# SCH_Atari_ST_sidecart_prototype_shared_b.net
KiCad netlist of a schematic drawn in EasyEDA
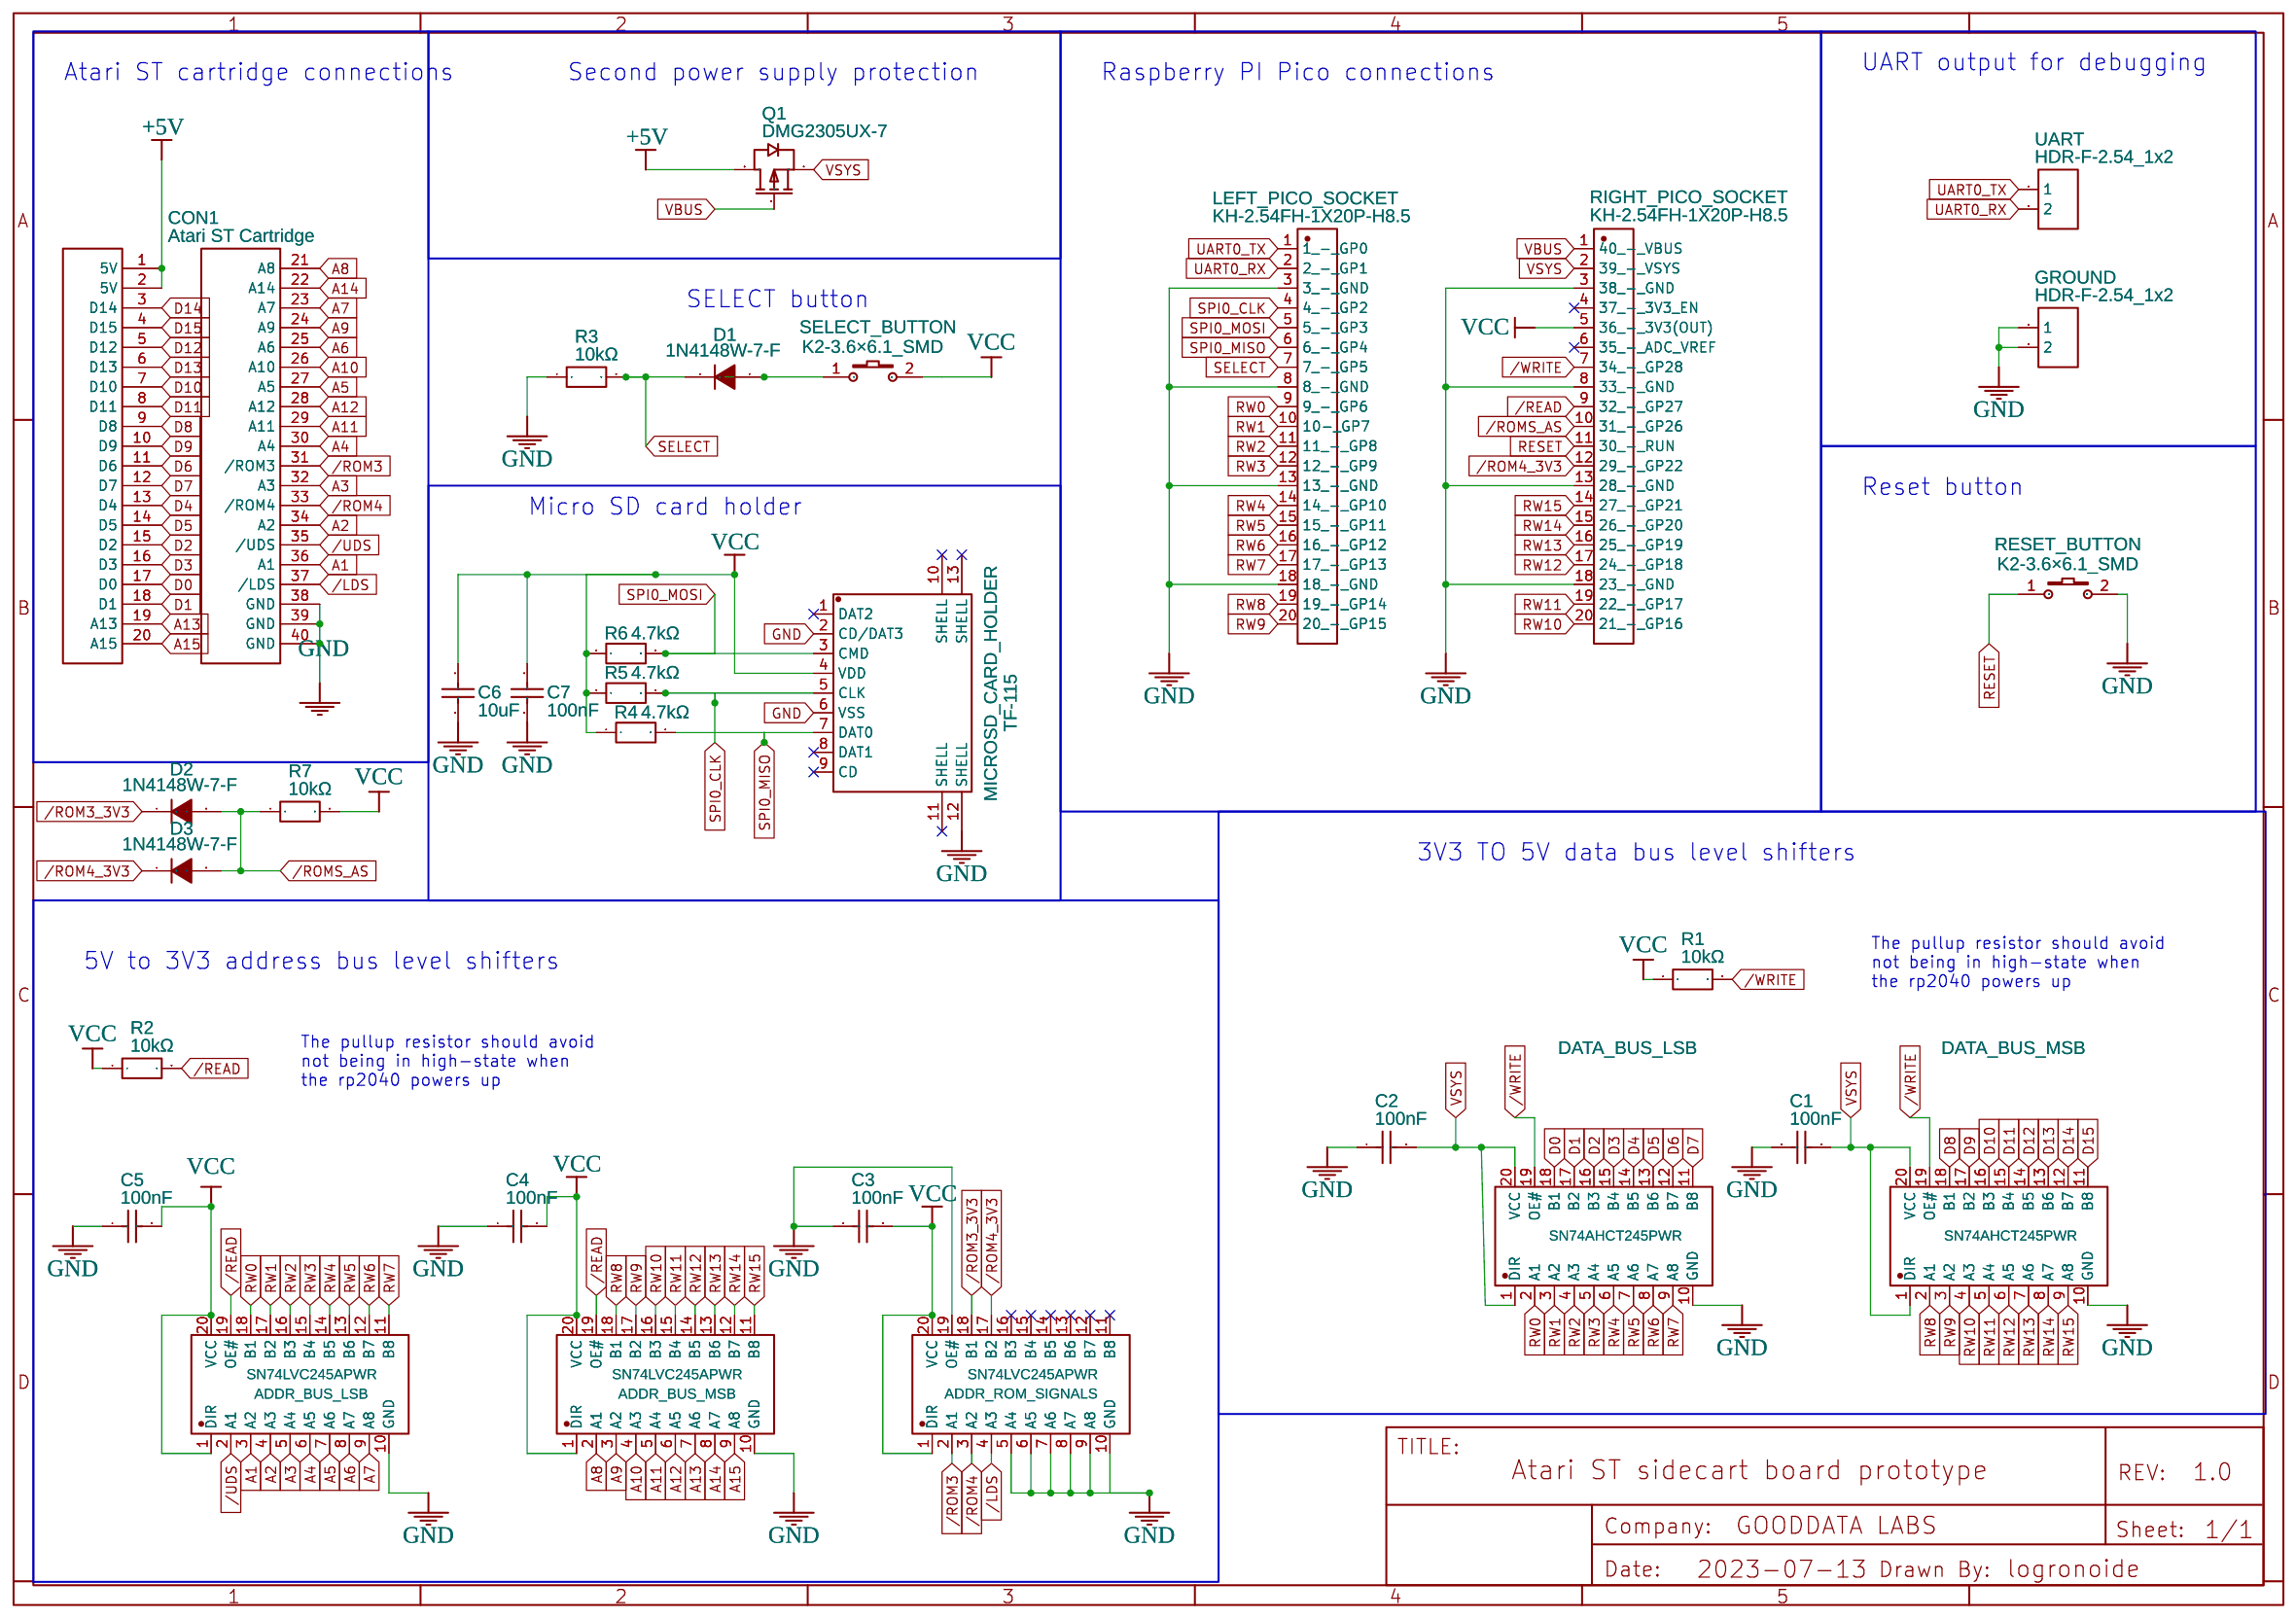
[diagram p0: schematic sheet]

(export (version "E")
  (design (tool "Eeschema 10.0.6"))
  (components
    (comp (ref "ADDR_BUS_LSB")
      (value "SN74LVC245APWR")
      (fields (field (name "Manufacturer") "TI(德州仪器)"))
      (libsource (lib "") (part "SN74LVC245ANG4_1"))
    )
    (comp (ref "ADDR_BUS_MSB")
      (value "SN74LVC245APWR")
      (fields (field (name "Manufacturer") "TI(德州仪器)"))
      (libsource (lib "") (part "SN74LVC245ANG4_2"))
    )
    (comp (ref "ADDR_ROM_SIGNALS")
      (value "SN74LVC245APWR")
      (fields (field (name "Manufacturer") "TI(德州仪器)"))
      (libsource (lib "") (part "SN74LVC245ANG4"))
    )
    (comp (ref "C1")
      (value "100nF")
      (fields
        (field (name "Manufacturer Part") "C0603C104K5RACAUTO")
        (field (name "Manufacturer") "KEMET(基美)")
      )
      (libsource (lib "") (part "C0603C104K5RACAUTO"))
    )
    (comp (ref "C2")
      (value "100nF")
      (fields
        (field (name "Manufacturer Part") "C0603C104K5RACAUTO")
        (field (name "Manufacturer") "KEMET(基美)")
      )
      (libsource (lib "") (part "C0603C104K5RACAUTO"))
    )
    (comp (ref "C3")
      (value "100nF")
      (fields
        (field (name "Manufacturer Part") "C0603C104K5RACAUTO")
        (field (name "Manufacturer") "KEMET(基美)")
      )
      (libsource (lib "") (part "C0603C104K5RACAUTO"))
    )
    (comp (ref "C4")
      (value "100nF")
      (fields
        (field (name "Manufacturer Part") "C0603C104K5RACAUTO")
        (field (name "Manufacturer") "KEMET(基美)")
      )
      (libsource (lib "") (part "C0603C104K5RACAUTO"))
    )
    (comp (ref "C5")
      (value "100nF")
      (fields
        (field (name "Manufacturer Part") "C0603C104K5RACAUTO")
        (field (name "Manufacturer") "KEMET(基美)")
      )
      (libsource (lib "") (part "C0603C104K5RACAUTO"))
    )
    (comp (ref "C6")
      (value "10uF")
      (fields
        (field (name "Manufacturer Part") "CC0603MRX5R7BB106")
        (field (name "Manufacturer") "YAGEO(国巨)")
      )
      (libsource (lib "") (part "CC0603MRX5R7BB106"))
    )
    (comp (ref "C7")
      (value "100nF")
      (fields
        (field (name "Manufacturer Part") "C0603C104K5RACAUTO")
        (field (name "Manufacturer") "KEMET(基美)")
      )
      (libsource (lib "") (part "C0603C104K5RACAUTO_1"))
    )
    (comp (ref "CON1") (value "Atari ST Cartridge") (libsource (lib "") (part "Unknown_90_-590")))
    (comp (ref "D1")
      (value "1N4148W-7-F")
      (fields (field (name "Manufacturer") "DIODES(美台)"))
      (libsource (lib "") (part "1N4148W-7-F"))
    )
    (comp (ref "D2")
      (value "1N4148W-7-F")
      (fields (field (name "Manufacturer") "DIODES(美台)"))
      (libsource (lib "") (part "1N4148W-7-F"))
    )
    (comp (ref "D3")
      (value "1N4148W-7-F")
      (fields (field (name "Manufacturer") "DIODES(美台)"))
      (libsource (lib "") (part "1N4148W-7-F"))
    )
    (comp (ref "DATA_BUS_LSB")
      (value "SN74AHCT245PWR")
      (fields (field (name "Manufacturer") "TI(德州仪器)"))
      (libsource (lib "") (part "SN74AHCT245N_1"))
    )
    (comp (ref "DATA_BUS_MSB")
      (value "SN74AHCT245PWR")
      (fields (field (name "Manufacturer") "TI(德州仪器)"))
      (libsource (lib "") (part "SN74AHCT245N"))
    )
    (comp (ref "GROUND") (value "HDR-F-2.54_1x2") (libsource (lib "") (part "HDR-F-2.54_1x2")))
    (comp (ref "LEFT_PICO_SOCKET")
      (value "KH-2.54FH-1X20P-H8.5")
      (fields (field (name "Manufacturer") "kinghelm(金航标)"))
      (libsource (lib "") (part "KH-2.54FH-1X20P-H8.5_1"))
    )
    (comp (ref "MICROSD_CARD_HOLDER")
      (value "TF-115")
      (fields (field (name "Manufacturer") "XUNPU(讯普)"))
      (libsource (lib "") (part "TF-115"))
    )
    (comp (ref "Q1")
      (value "DMG2305UX-7")
      (fields (field (name "Manufacturer") "DIODES(美台)"))
      (libsource (lib "") (part "DMG2305UX-7"))
    )
    (comp (ref "R1")
      (value "10kΩ")
      (fields (field (name "Manufacturer Part") "RT0603DRE0710KL") (field (name "Manufacturer") "YAGEO(国巨)"))
      (libsource (lib "") (part "RT0603DRE0710KL"))
    )
    (comp (ref "R2")
      (value "10kΩ")
      (fields (field (name "Manufacturer Part") "RT0603DRE0710KL") (field (name "Manufacturer") "YAGEO(国巨)"))
      (libsource (lib "") (part "RT0603DRE0710KL"))
    )
    (comp (ref "R3")
      (value "10kΩ")
      (fields (field (name "Manufacturer Part") "RT0603DRE0710KL") (field (name "Manufacturer") "YAGEO(国巨)"))
      (libsource (lib "") (part "RT0603DRE0710KL"))
    )
    (comp (ref "R4")
      (value "4.7kΩ")
      (fields
        (field (name "Manufacturer Part") "CR0603F4K70P05Z")
        (field (name "Manufacturer") "EVER OHMS(天二科技)")
      )
      (libsource (lib "") (part "CR0603F4K70P05Z"))
    )
    (comp (ref "R5")
      (value "4.7kΩ")
      (fields
        (field (name "Manufacturer Part") "CR0603F4K70P05Z")
        (field (name "Manufacturer") "EVER OHMS(天二科技)")
      )
      (libsource (lib "") (part "CR0603F4K70P05Z"))
    )
    (comp (ref "R6")
      (value "4.7kΩ")
      (fields
        (field (name "Manufacturer Part") "CR0603F4K70P05Z")
        (field (name "Manufacturer") "EVER OHMS(天二科技)")
      )
      (libsource (lib "") (part "CR0603F4K70P05Z"))
    )
    (comp (ref "R7")
      (value "10kΩ")
      (fields (field (name "Manufacturer Part") "RT0603DRE0710KL") (field (name "Manufacturer") "YAGEO(国巨)"))
      (libsource (lib "") (part "RT0603DRE0710KL"))
    )
    (comp (ref "RESET_BUTTON")
      (value "K2-3.6×6.1_SMD")
      (fields (field (name "Manufacturer Part") "K2-1107ST-A4SW-06"))
      (libsource (lib "") (part "K2-3.6×6.1_SMD_1"))
    )
    (comp (ref "RIGHT_PICO_SOCKET")
      (value "KH-2.54FH-1X20P-H8.5")
      (fields (field (name "Manufacturer") "kinghelm(金航标)"))
      (libsource (lib "") (part "KH-2.54FH-1X20P-H8.5"))
    )
    (comp (ref "SELECT_BUTTON")
      (value "K2-3.6×6.1_SMD")
      (fields (field (name "Manufacturer Part") "K2-1107ST-A4SW-06"))
      (libsource (lib "") (part "K2-3.6×6.1_SMD"))
    )
    (comp (ref "UART") (value "HDR-F-2.54_1x2") (libsource (lib "") (part "HDR-F-2.54_1x2_1")))
  )
  (nets
    (net (code "1") (name "+5V") (class "Default")
      (node (ref "CON1") (pin "1") (pinfunction "5V_1") (pintype "unspecified"))
      (node (ref "CON1") (pin "2") (pinfunction "5V_2") (pintype "unspecified"))
      (node (ref "Q1") (pin "3") (pinfunction "D_3") (pintype "unspecified"))
    )
    (net (code "2") (name "A1") (class "Default")
      (node (ref "ADDR_BUS_LSB") (pin "3") (pinfunction "A2_3") (pintype "unspecified"))
      (node (ref "CON1") (pin "36") (pinfunction "A1_36") (pintype "unspecified"))
    )
    (net (code "3") (name "A2") (class "Default")
      (node (ref "ADDR_BUS_LSB") (pin "4") (pinfunction "A3_4") (pintype "unspecified"))
      (node (ref "CON1") (pin "34") (pinfunction "A2_34") (pintype "unspecified"))
    )
    (net (code "4") (name "A3") (class "Default")
      (node (ref "ADDR_BUS_LSB") (pin "5") (pinfunction "A4_5") (pintype "unspecified"))
      (node (ref "CON1") (pin "32") (pinfunction "A3_32") (pintype "unspecified"))
    )
    (net (code "5") (name "A4") (class "Default")
      (node (ref "ADDR_BUS_LSB") (pin "6") (pinfunction "A5_6") (pintype "unspecified"))
      (node (ref "CON1") (pin "30") (pinfunction "A4_30") (pintype "unspecified"))
    )
    (net (code "6") (name "A5") (class "Default")
      (node (ref "ADDR_BUS_LSB") (pin "7") (pinfunction "A6_7") (pintype "unspecified"))
      (node (ref "CON1") (pin "27") (pinfunction "A5_27") (pintype "unspecified"))
    )
    (net (code "7") (name "A6") (class "Default")
      (node (ref "ADDR_BUS_LSB") (pin "8") (pinfunction "A7_8") (pintype "unspecified"))
      (node (ref "CON1") (pin "25") (pinfunction "A6_25") (pintype "unspecified"))
    )
    (net (code "8") (name "A7") (class "Default")
      (node (ref "ADDR_BUS_LSB") (pin "9") (pinfunction "A8_9") (pintype "unspecified"))
      (node (ref "CON1") (pin "23") (pinfunction "A7_23") (pintype "unspecified"))
    )
    (net (code "9") (name "A8") (class "Default")
      (node (ref "ADDR_BUS_MSB") (pin "2") (pinfunction "A1_2") (pintype "unspecified"))
      (node (ref "CON1") (pin "21") (pinfunction "A8_21") (pintype "unspecified"))
    )
    (net (code "10") (name "A9") (class "Default")
      (node (ref "ADDR_BUS_MSB") (pin "3") (pinfunction "A2_3") (pintype "unspecified"))
      (node (ref "CON1") (pin "24") (pinfunction "A9_24") (pintype "unspecified"))
    )
    (net (code "11") (name "A10") (class "Default")
      (node (ref "ADDR_BUS_MSB") (pin "4") (pinfunction "A3_4") (pintype "unspecified"))
      (node (ref "CON1") (pin "26") (pinfunction "A10_26") (pintype "unspecified"))
    )
    (net (code "12") (name "A11") (class "Default")
      (node (ref "ADDR_BUS_MSB") (pin "5") (pinfunction "A4_5") (pintype "unspecified"))
      (node (ref "CON1") (pin "29") (pinfunction "A11_29") (pintype "unspecified"))
    )
    (net (code "13") (name "A12") (class "Default")
      (node (ref "ADDR_BUS_MSB") (pin "6") (pinfunction "A5_6") (pintype "unspecified"))
      (node (ref "CON1") (pin "28") (pinfunction "A12_28") (pintype "unspecified"))
    )
    (net (code "14") (name "A13") (class "Default")
      (node (ref "ADDR_BUS_MSB") (pin "7") (pinfunction "A6_7") (pintype "unspecified"))
      (node (ref "CON1") (pin "19") (pinfunction "A13_19") (pintype "unspecified"))
    )
    (net (code "15") (name "A14") (class "Default")
      (node (ref "ADDR_BUS_MSB") (pin "8") (pinfunction "A7_8") (pintype "unspecified"))
      (node (ref "CON1") (pin "22") (pinfunction "A14_22") (pintype "unspecified"))
    )
    (net (code "16") (name "A15") (class "Default")
      (node (ref "ADDR_BUS_MSB") (pin "9") (pinfunction "A8_9") (pintype "unspecified"))
      (node (ref "CON1") (pin "20") (pinfunction "A15_20") (pintype "unspecified"))
    )
    (net (code "17") (name "D0") (class "Default")
      (node (ref "CON1") (pin "17") (pinfunction "D0_17") (pintype "unspecified"))
      (node (ref "DATA_BUS_LSB") (pin "18") (pinfunction "B1_18") (pintype "unspecified"))
    )
    (net (code "18") (name "D1") (class "Default")
      (node (ref "CON1") (pin "18") (pinfunction "D1_18") (pintype "unspecified"))
      (node (ref "DATA_BUS_LSB") (pin "17") (pinfunction "B2_17") (pintype "unspecified"))
    )
    (net (code "19") (name "D2") (class "Default")
      (node (ref "CON1") (pin "15") (pinfunction "D2_15") (pintype "unspecified"))
      (node (ref "DATA_BUS_LSB") (pin "16") (pinfunction "B3_16") (pintype "unspecified"))
    )
    (net (code "20") (name "D3") (class "Default")
      (node (ref "CON1") (pin "16") (pinfunction "D3_16") (pintype "unspecified"))
      (node (ref "DATA_BUS_LSB") (pin "15") (pinfunction "B4_15") (pintype "unspecified"))
    )
    (net (code "21") (name "D4") (class "Default")
      (node (ref "CON1") (pin "13") (pinfunction "D4_13") (pintype "unspecified"))
      (node (ref "DATA_BUS_LSB") (pin "14") (pinfunction "B5_14") (pintype "unspecified"))
    )
    (net (code "22") (name "D5") (class "Default")
      (node (ref "CON1") (pin "14") (pinfunction "D5_14") (pintype "unspecified"))
      (node (ref "DATA_BUS_LSB") (pin "13") (pinfunction "B6_13") (pintype "unspecified"))
    )
    (net (code "23") (name "D6") (class "Default")
      (node (ref "CON1") (pin "11") (pinfunction "D6_11") (pintype "unspecified"))
      (node (ref "DATA_BUS_LSB") (pin "12") (pinfunction "B7_12") (pintype "unspecified"))
    )
    (net (code "24") (name "D7") (class "Default")
      (node (ref "CON1") (pin "12") (pinfunction "D7_12") (pintype "unspecified"))
      (node (ref "DATA_BUS_LSB") (pin "11") (pinfunction "B8_11") (pintype "unspecified"))
    )
    (net (code "25") (name "D8") (class "Default")
      (node (ref "CON1") (pin "9") (pinfunction "D8_9") (pintype "unspecified"))
      (node (ref "DATA_BUS_MSB") (pin "18") (pinfunction "B1_18") (pintype "unspecified"))
    )
    (net (code "26") (name "D9") (class "Default")
      (node (ref "CON1") (pin "10") (pinfunction "D9_10") (pintype "unspecified"))
      (node (ref "DATA_BUS_MSB") (pin "17") (pinfunction "B2_17") (pintype "unspecified"))
    )
    (net (code "27") (name "D10") (class "Default")
      (node (ref "CON1") (pin "7") (pinfunction "D10_7") (pintype "unspecified"))
      (node (ref "DATA_BUS_MSB") (pin "16") (pinfunction "B3_16") (pintype "unspecified"))
    )
    (net (code "28") (name "D11") (class "Default")
      (node (ref "CON1") (pin "8") (pinfunction "D11_8") (pintype "unspecified"))
      (node (ref "DATA_BUS_MSB") (pin "15") (pinfunction "B4_15") (pintype "unspecified"))
    )
    (net (code "29") (name "D12") (class "Default")
      (node (ref "CON1") (pin "5") (pinfunction "D12_5") (pintype "unspecified"))
      (node (ref "DATA_BUS_MSB") (pin "14") (pinfunction "B5_14") (pintype "unspecified"))
    )
    (net (code "30") (name "D13") (class "Default")
      (node (ref "CON1") (pin "6") (pinfunction "D13_6") (pintype "unspecified"))
      (node (ref "DATA_BUS_MSB") (pin "13") (pinfunction "B6_13") (pintype "unspecified"))
    )
    (net (code "31") (name "D14") (class "Default")
      (node (ref "CON1") (pin "3") (pinfunction "D14_3") (pintype "unspecified"))
      (node (ref "DATA_BUS_MSB") (pin "12") (pinfunction "B7_12") (pintype "unspecified"))
    )
    (net (code "32") (name "D15") (class "Default")
      (node (ref "CON1") (pin "4") (pinfunction "D15_4") (pintype "unspecified"))
      (node (ref "DATA_BUS_MSB") (pin "11") (pinfunction "B8_11") (pintype "unspecified"))
    )
    (net (code "33") (name "GND") (class "Default")
      (node (ref "ADDR_BUS_LSB") (pin "10") (pinfunction "GND_10") (pintype "unspecified"))
      (node (ref "ADDR_BUS_MSB") (pin "10") (pinfunction "GND_10") (pintype "unspecified"))
      (node (ref "ADDR_ROM_SIGNALS") (pin "10") (pinfunction "GND_10") (pintype "unspecified"))
      (node (ref "ADDR_ROM_SIGNALS") (pin "19") (pinfunction "OE#_19") (pintype "unspecified"))
      (node (ref "ADDR_ROM_SIGNALS") (pin "5") (pinfunction "A4_5") (pintype "unspecified"))
      (node (ref "ADDR_ROM_SIGNALS") (pin "6") (pinfunction "A5_6") (pintype "unspecified"))
      (node (ref "ADDR_ROM_SIGNALS") (pin "7") (pinfunction "A6_7") (pintype "unspecified"))
      (node (ref "ADDR_ROM_SIGNALS") (pin "8") (pinfunction "A7_8") (pintype "unspecified"))
      (node (ref "ADDR_ROM_SIGNALS") (pin "9") (pinfunction "A8_9") (pintype "unspecified"))
      (node (ref "C1") (pin "1") (pinfunction "1_1") (pintype "input"))
      (node (ref "C2") (pin "1") (pinfunction "1_1") (pintype "input"))
      (node (ref "C3") (pin "1") (pinfunction "1_1") (pintype "input"))
      (node (ref "C4") (pin "1") (pinfunction "1_1") (pintype "input"))
      (node (ref "C5") (pin "1") (pinfunction "1_1") (pintype "input"))
      (node (ref "C6") (pin "1") (pinfunction "1_1") (pintype "input"))
      (node (ref "C7") (pin "1") (pinfunction "1_1") (pintype "input"))
      (node (ref "CON1") (pin "38") (pinfunction "GND_38") (pintype "unspecified"))
      (node (ref "CON1") (pin "39") (pinfunction "GND_39") (pintype "unspecified"))
      (node (ref "CON1") (pin "40") (pinfunction "GND_40") (pintype "unspecified"))
      (node (ref "DATA_BUS_LSB") (pin "10") (pinfunction "GND_10") (pintype "unspecified"))
      (node (ref "DATA_BUS_MSB") (pin "10") (pinfunction "GND_10") (pintype "unspecified"))
      (node (ref "GROUND") (pin "1") (pinfunction "1_1") (pintype "input"))
      (node (ref "GROUND") (pin "2") (pinfunction "2_2") (pintype "input"))
      (node (ref "LEFT_PICO_SOCKET") (pin "13") (pinfunction "13_-_GND_13") (pintype "unspecified"))
      (node (ref "LEFT_PICO_SOCKET") (pin "18") (pinfunction "18_-_GND_18") (pintype "unspecified"))
      (node (ref "LEFT_PICO_SOCKET") (pin "3") (pinfunction "3_-_GND_3") (pintype "unspecified"))
      (node (ref "LEFT_PICO_SOCKET") (pin "8") (pinfunction "8_-_GND_8") (pintype "unspecified"))
      (node (ref "MICROSD_CARD_HOLDER") (pin "12") (pinfunction "SHELL_12") (pintype "unspecified"))
      (node (ref "MICROSD_CARD_HOLDER") (pin "2") (pinfunction "CD/DAT3_2") (pintype "unspecified"))
      (node (ref "MICROSD_CARD_HOLDER") (pin "6") (pinfunction "VSS_6") (pintype "unspecified"))
      (node (ref "R3") (pin "1") (pinfunction "1_1") (pintype "unspecified"))
      (node (ref "RESET_BUTTON") (pin "2") (pinfunction "2_2") (pintype "unspecified"))
      (node (ref "RIGHT_PICO_SOCKET") (pin "13") (pinfunction "28_-_GND_13") (pintype "unspecified"))
      (node (ref "RIGHT_PICO_SOCKET") (pin "18") (pinfunction "23_-_GND_18") (pintype "unspecified"))
      (node (ref "RIGHT_PICO_SOCKET") (pin "3") (pinfunction "38_-_GND_3") (pintype "unspecified"))
      (node (ref "RIGHT_PICO_SOCKET") (pin "8") (pinfunction "33_-_GND_8") (pintype "unspecified"))
    )
    (net (code "34") (name "Net-(D1-A)") (class "Default")
      (node (ref "D1") (pin "2") (pinfunction "A_2") (pintype "unspecified"))
      (node (ref "SELECT_BUTTON") (pin "1") (pinfunction "1_1") (pintype "unspecified"))
    )
    (net (code "35") (name "RESET") (class "Default")
      (node (ref "RESET_BUTTON") (pin "1") (pinfunction "1_1") (pintype "unspecified"))
      (node (ref "RIGHT_PICO_SOCKET") (pin "11") (pinfunction "30_-_RUN_11") (pintype "unspecified"))
    )
    (net (code "36") (name "RW0") (class "Default")
      (node (ref "ADDR_BUS_LSB") (pin "18") (pinfunction "B1_18") (pintype "unspecified"))
      (node (ref "DATA_BUS_LSB") (pin "2") (pinfunction "A1_2") (pintype "unspecified"))
      (node (ref "LEFT_PICO_SOCKET") (pin "9") (pinfunction "9_-_GP6_9") (pintype "unspecified"))
    )
    (net (code "37") (name "RW1") (class "Default")
      (node (ref "ADDR_BUS_LSB") (pin "17") (pinfunction "B2_17") (pintype "unspecified"))
      (node (ref "DATA_BUS_LSB") (pin "3") (pinfunction "A2_3") (pintype "unspecified"))
      (node (ref "LEFT_PICO_SOCKET") (pin "10") (pinfunction "10-_GP7_10") (pintype "unspecified"))
    )
    (net (code "38") (name "RW2") (class "Default")
      (node (ref "ADDR_BUS_LSB") (pin "16") (pinfunction "B3_16") (pintype "unspecified"))
      (node (ref "DATA_BUS_LSB") (pin "4") (pinfunction "A3_4") (pintype "unspecified"))
      (node (ref "LEFT_PICO_SOCKET") (pin "11") (pinfunction "11_-_GP8_11") (pintype "unspecified"))
    )
    (net (code "39") (name "RW3") (class "Default")
      (node (ref "ADDR_BUS_LSB") (pin "15") (pinfunction "B4_15") (pintype "unspecified"))
      (node (ref "DATA_BUS_LSB") (pin "5") (pinfunction "A4_5") (pintype "unspecified"))
      (node (ref "LEFT_PICO_SOCKET") (pin "12") (pinfunction "12_-_GP9_12") (pintype "unspecified"))
    )
    (net (code "40") (name "RW4") (class "Default")
      (node (ref "ADDR_BUS_LSB") (pin "14") (pinfunction "B5_14") (pintype "unspecified"))
      (node (ref "DATA_BUS_LSB") (pin "6") (pinfunction "A5_6") (pintype "unspecified"))
      (node (ref "LEFT_PICO_SOCKET") (pin "14") (pinfunction "14_-_GP10_14") (pintype "unspecified"))
    )
    (net (code "41") (name "RW5") (class "Default")
      (node (ref "ADDR_BUS_LSB") (pin "13") (pinfunction "B6_13") (pintype "unspecified"))
      (node (ref "DATA_BUS_LSB") (pin "7") (pinfunction "A6_7") (pintype "unspecified"))
      (node (ref "LEFT_PICO_SOCKET") (pin "15") (pinfunction "15_-_GP11_15") (pintype "unspecified"))
    )
    (net (code "42") (name "RW6") (class "Default")
      (node (ref "ADDR_BUS_LSB") (pin "12") (pinfunction "B7_12") (pintype "unspecified"))
      (node (ref "DATA_BUS_LSB") (pin "8") (pinfunction "A7_8") (pintype "unspecified"))
      (node (ref "LEFT_PICO_SOCKET") (pin "16") (pinfunction "16_-_GP12_16") (pintype "unspecified"))
    )
    (net (code "43") (name "RW7") (class "Default")
      (node (ref "ADDR_BUS_LSB") (pin "11") (pinfunction "B8_11") (pintype "unspecified"))
      (node (ref "DATA_BUS_LSB") (pin "9") (pinfunction "A8_9") (pintype "unspecified"))
      (node (ref "LEFT_PICO_SOCKET") (pin "17") (pinfunction "17_-_GP13_17") (pintype "unspecified"))
    )
    (net (code "44") (name "RW8") (class "Default")
      (node (ref "ADDR_BUS_MSB") (pin "18") (pinfunction "B1_18") (pintype "unspecified"))
      (node (ref "DATA_BUS_MSB") (pin "2") (pinfunction "A1_2") (pintype "unspecified"))
      (node (ref "LEFT_PICO_SOCKET") (pin "19") (pinfunction "19_-_GP14_19") (pintype "unspecified"))
    )
    (net (code "45") (name "RW9") (class "Default")
      (node (ref "ADDR_BUS_MSB") (pin "17") (pinfunction "B2_17") (pintype "unspecified"))
      (node (ref "DATA_BUS_MSB") (pin "3") (pinfunction "A2_3") (pintype "unspecified"))
      (node (ref "LEFT_PICO_SOCKET") (pin "20") (pinfunction "20_-_GP15_20") (pintype "unspecified"))
    )
    (net (code "46") (name "RW10") (class "Default")
      (node (ref "ADDR_BUS_MSB") (pin "16") (pinfunction "B3_16") (pintype "unspecified"))
      (node (ref "DATA_BUS_MSB") (pin "4") (pinfunction "A3_4") (pintype "unspecified"))
      (node (ref "RIGHT_PICO_SOCKET") (pin "20") (pinfunction "21_-_GP16_20") (pintype "unspecified"))
    )
    (net (code "47") (name "RW11") (class "Default")
      (node (ref "ADDR_BUS_MSB") (pin "15") (pinfunction "B4_15") (pintype "unspecified"))
      (node (ref "DATA_BUS_MSB") (pin "5") (pinfunction "A4_5") (pintype "unspecified"))
      (node (ref "RIGHT_PICO_SOCKET") (pin "19") (pinfunction "22_-_GP17_19") (pintype "unspecified"))
    )
    (net (code "48") (name "RW12") (class "Default")
      (node (ref "ADDR_BUS_MSB") (pin "14") (pinfunction "B5_14") (pintype "unspecified"))
      (node (ref "DATA_BUS_MSB") (pin "6") (pinfunction "A5_6") (pintype "unspecified"))
      (node (ref "RIGHT_PICO_SOCKET") (pin "17") (pinfunction "24_-_GP18_17") (pintype "unspecified"))
    )
    (net (code "49") (name "RW13") (class "Default")
      (node (ref "ADDR_BUS_MSB") (pin "13") (pinfunction "B6_13") (pintype "unspecified"))
      (node (ref "DATA_BUS_MSB") (pin "7") (pinfunction "A6_7") (pintype "unspecified"))
      (node (ref "RIGHT_PICO_SOCKET") (pin "16") (pinfunction "25_-_GP19_16") (pintype "unspecified"))
    )
    (net (code "50") (name "RW14") (class "Default")
      (node (ref "ADDR_BUS_MSB") (pin "12") (pinfunction "B7_12") (pintype "unspecified"))
      (node (ref "DATA_BUS_MSB") (pin "8") (pinfunction "A7_8") (pintype "unspecified"))
      (node (ref "RIGHT_PICO_SOCKET") (pin "15") (pinfunction "26_-_GP20_15") (pintype "unspecified"))
    )
    (net (code "51") (name "RW15") (class "Default")
      (node (ref "ADDR_BUS_MSB") (pin "11") (pinfunction "B8_11") (pintype "unspecified"))
      (node (ref "DATA_BUS_MSB") (pin "9") (pinfunction "A8_9") (pintype "unspecified"))
      (node (ref "RIGHT_PICO_SOCKET") (pin "14") (pinfunction "27_-_GP21_14") (pintype "unspecified"))
    )
    (net (code "52") (name "SELECT") (class "Default")
      (node (ref "D1") (pin "1") (pinfunction "C_1") (pintype "unspecified"))
      (node (ref "LEFT_PICO_SOCKET") (pin "7") (pinfunction "7_-_GP5_7") (pintype "unspecified"))
      (node (ref "R3") (pin "2") (pinfunction "2_2") (pintype "unspecified"))
    )
    (net (code "53") (name "SPI0_CLK") (class "Default")
      (node (ref "LEFT_PICO_SOCKET") (pin "4") (pinfunction "4_-_GP2_4") (pintype "unspecified"))
      (node (ref "MICROSD_CARD_HOLDER") (pin "5") (pinfunction "CLK_5") (pintype "unspecified"))
      (node (ref "R5") (pin "2") (pinfunction "2_2") (pintype "unspecified"))
    )
    (net (code "54") (name "SPI0_MISO") (class "Default")
      (node (ref "LEFT_PICO_SOCKET") (pin "6") (pinfunction "6_-_GP4_6") (pintype "unspecified"))
      (node (ref "MICROSD_CARD_HOLDER") (pin "7") (pinfunction "DAT0_7") (pintype "unspecified"))
      (node (ref "R4") (pin "2") (pinfunction "2_2") (pintype "unspecified"))
    )
    (net (code "55") (name "SPI0_MOSI") (class "Default")
      (node (ref "LEFT_PICO_SOCKET") (pin "5") (pinfunction "5_-_GP3_5") (pintype "unspecified"))
      (node (ref "MICROSD_CARD_HOLDER") (pin "3") (pinfunction "CMD_3") (pintype "unspecified"))
      (node (ref "R6") (pin "2") (pinfunction "2_2") (pintype "unspecified"))
    )
    (net (code "56") (name "UART0_RX") (class "Default")
      (node (ref "LEFT_PICO_SOCKET") (pin "2") (pinfunction "2_-_GP1_2") (pintype "unspecified"))
      (node (ref "UART") (pin "2") (pinfunction "2_2") (pintype "input"))
    )
    (net (code "57") (name "UART0_TX") (class "Default")
      (node (ref "LEFT_PICO_SOCKET") (pin "1") (pinfunction "1_-_GP0_1") (pintype "unspecified"))
      (node (ref "UART") (pin "1") (pinfunction "1_1") (pintype "input"))
    )
    (net (code "58") (name "VBUS") (class "Default")
      (node (ref "Q1") (pin "1") (pinfunction "G_1") (pintype "unspecified"))
      (node (ref "RIGHT_PICO_SOCKET") (pin "1") (pinfunction "40_-_VBUS_1") (pintype "unspecified"))
    )
    (net (code "59") (name "VCC") (class "Default")
      (node (ref "ADDR_BUS_LSB") (pin "1") (pinfunction "DIR_1") (pintype "unspecified"))
      (node (ref "ADDR_BUS_LSB") (pin "20") (pinfunction "VCC_20") (pintype "unspecified"))
      (node (ref "ADDR_BUS_MSB") (pin "1") (pinfunction "DIR_1") (pintype "unspecified"))
      (node (ref "ADDR_BUS_MSB") (pin "20") (pinfunction "VCC_20") (pintype "unspecified"))
      (node (ref "ADDR_ROM_SIGNALS") (pin "1") (pinfunction "DIR_1") (pintype "unspecified"))
      (node (ref "ADDR_ROM_SIGNALS") (pin "20") (pinfunction "VCC_20") (pintype "unspecified"))
      (node (ref "C3") (pin "2") (pinfunction "2_2") (pintype "input"))
      (node (ref "C4") (pin "2") (pinfunction "2_2") (pintype "input"))
      (node (ref "C5") (pin "2") (pinfunction "2_2") (pintype "input"))
      (node (ref "C6") (pin "2") (pinfunction "2_2") (pintype "input"))
      (node (ref "C7") (pin "2") (pinfunction "2_2") (pintype "input"))
      (node (ref "MICROSD_CARD_HOLDER") (pin "4") (pinfunction "VDD_4") (pintype "unspecified"))
      (node (ref "R1") (pin "1") (pinfunction "1_1") (pintype "unspecified"))
      (node (ref "R2") (pin "1") (pinfunction "1_1") (pintype "unspecified"))
      (node (ref "R4") (pin "1") (pinfunction "1_1") (pintype "unspecified"))
      (node (ref "R5") (pin "1") (pinfunction "1_1") (pintype "unspecified"))
      (node (ref "R6") (pin "1") (pinfunction "1_1") (pintype "unspecified"))
      (node (ref "R7") (pin "2") (pinfunction "2_2") (pintype "unspecified"))
      (node (ref "RIGHT_PICO_SOCKET") (pin "5") (pinfunction "36_-_3V3(OUT)_5") (pintype "unspecified"))
      (node (ref "SELECT_BUTTON") (pin "2") (pinfunction "2_2") (pintype "unspecified"))
    )
    (net (code "60") (name "VSYS") (class "Default")
      (node (ref "C1") (pin "2") (pinfunction "2_2") (pintype "input"))
      (node (ref "C2") (pin "2") (pinfunction "2_2") (pintype "input"))
      (node (ref "DATA_BUS_LSB") (pin "1") (pinfunction "DIR_1") (pintype "unspecified"))
      (node (ref "DATA_BUS_LSB") (pin "20") (pinfunction "VCC_20") (pintype "unspecified"))
      (node (ref "DATA_BUS_MSB") (pin "1") (pinfunction "DIR_1") (pintype "unspecified"))
      (node (ref "DATA_BUS_MSB") (pin "20") (pinfunction "VCC_20") (pintype "unspecified"))
      (node (ref "Q1") (pin "2") (pinfunction "S_2") (pintype "unspecified"))
      (node (ref "RIGHT_PICO_SOCKET") (pin "2") (pinfunction "39_-_VSYS_2") (pintype "unspecified"))
    )
    (net (code "61") (name "unconnected-(ADDR_ROM_SIGNALS-B3-Pad16)") (class "Default")
      (node (ref "ADDR_ROM_SIGNALS") (pin "16") (pinfunction "B3_16") (pintype "unspecified+no_connect"))
    )
    (net (code "62") (name "unconnected-(ADDR_ROM_SIGNALS-B4-Pad15)") (class "Default")
      (node (ref "ADDR_ROM_SIGNALS") (pin "15") (pinfunction "B4_15") (pintype "unspecified+no_connect"))
    )
    (net (code "63") (name "unconnected-(ADDR_ROM_SIGNALS-B5-Pad14)") (class "Default")
      (node (ref "ADDR_ROM_SIGNALS") (pin "14") (pinfunction "B5_14") (pintype "unspecified+no_connect"))
    )
    (net (code "64") (name "unconnected-(ADDR_ROM_SIGNALS-B6-Pad13)") (class "Default")
      (node (ref "ADDR_ROM_SIGNALS") (pin "13") (pinfunction "B6_13") (pintype "unspecified+no_connect"))
    )
    (net (code "65") (name "unconnected-(ADDR_ROM_SIGNALS-B7-Pad12)") (class "Default")
      (node (ref "ADDR_ROM_SIGNALS") (pin "12") (pinfunction "B7_12") (pintype "unspecified+no_connect"))
    )
    (net (code "66") (name "unconnected-(ADDR_ROM_SIGNALS-B8-Pad11)") (class "Default")
      (node (ref "ADDR_ROM_SIGNALS") (pin "11") (pinfunction "B8_11") (pintype "unspecified+no_connect"))
    )
    (net (code "67") (name "unconnected-(MICROSD_CARD_HOLDER-CD-Pad9)") (class "Default")
      (node (ref "MICROSD_CARD_HOLDER") (pin "9") (pinfunction "CD_9") (pintype "unspecified+no_connect"))
    )
    (net (code "68") (name "unconnected-(MICROSD_CARD_HOLDER-DAT1-Pad8)") (class "Default")
      (node (ref "MICROSD_CARD_HOLDER") (pin "8") (pinfunction "DAT1_8") (pintype "unspecified+no_connect"))
    )
    (net (code "69") (name "unconnected-(MICROSD_CARD_HOLDER-DAT2-Pad1)") (class "Default")
      (node (ref "MICROSD_CARD_HOLDER") (pin "1") (pinfunction "DAT2_1") (pintype "unspecified+no_connect"))
    )
    (net (code "70") (name "unconnected-(MICROSD_CARD_HOLDER-SHELL-Pad10)") (class "Default")
      (node (ref "MICROSD_CARD_HOLDER") (pin "10") (pinfunction "SHELL_10") (pintype "unspecified+no_connect"))
    )
    (net (code "71") (name "unconnected-(MICROSD_CARD_HOLDER-SHELL-Pad11)") (class "Default")
      (node (ref "MICROSD_CARD_HOLDER") (pin "11") (pinfunction "SHELL_11") (pintype "unspecified+no_connect"))
    )
    (net (code "72") (name "unconnected-(MICROSD_CARD_HOLDER-SHELL-Pad13)") (class "Default")
      (node (ref "MICROSD_CARD_HOLDER") (pin "13") (pinfunction "SHELL_13") (pintype "unspecified+no_connect"))
    )
    (net (code "73") (name "unconnected-(RIGHT_PICO_SOCKET-35_-_ADC_VREF-Pad6)") (class "Default")
      (node (ref "RIGHT_PICO_SOCKET") (pin "6") (pinfunction "35_-_ADC_VREF_6") (pintype "unspecified+no_connect"))
    )
    (net (code "74") (name "unconnected-(RIGHT_PICO_SOCKET-37_-_3V3_EN-Pad4)") (class "Default")
      (node (ref "RIGHT_PICO_SOCKET") (pin "4") (pinfunction "37_-_3V3_EN_4") (pintype "unspecified+no_connect"))
    )
    (net (code "75") (name "{slash}LDS") (class "Default")
      (node (ref "ADDR_ROM_SIGNALS") (pin "4") (pinfunction "A3_4") (pintype "unspecified"))
      (node (ref "CON1") (pin "37") (pinfunction "/LDS_37") (pintype "unspecified"))
    )
    (net (code "76") (name "{slash}READ") (class "Default")
      (node (ref "ADDR_BUS_LSB") (pin "19") (pinfunction "OE#_19") (pintype "unspecified"))
      (node (ref "ADDR_BUS_MSB") (pin "19") (pinfunction "OE#_19") (pintype "unspecified"))
      (node (ref "R2") (pin "2") (pinfunction "2_2") (pintype "unspecified"))
      (node (ref "RIGHT_PICO_SOCKET") (pin "9") (pinfunction "32_-_GP27_9") (pintype "unspecified"))
    )
    (net (code "77") (name "{slash}ROM3") (class "Default")
      (node (ref "ADDR_ROM_SIGNALS") (pin "2") (pinfunction "A1_2") (pintype "unspecified"))
      (node (ref "CON1") (pin "31") (pinfunction "/ROM3_31") (pintype "unspecified"))
    )
    (net (code "78") (name "{slash}ROM3_3V3") (class "Default")
      (node (ref "ADDR_ROM_SIGNALS") (pin "18") (pinfunction "B1_18") (pintype "unspecified"))
      (node (ref "D2") (pin "1") (pinfunction "C_1") (pintype "unspecified"))
    )
    (net (code "79") (name "{slash}ROM4") (class "Default")
      (node (ref "ADDR_ROM_SIGNALS") (pin "3") (pinfunction "A2_3") (pintype "unspecified"))
      (node (ref "CON1") (pin "33") (pinfunction "/ROM4_33") (pintype "unspecified"))
    )
    (net (code "80") (name "{slash}ROM4_3V3") (class "Default")
      (node (ref "ADDR_ROM_SIGNALS") (pin "17") (pinfunction "B2_17") (pintype "unspecified"))
      (node (ref "D3") (pin "1") (pinfunction "C_1") (pintype "unspecified"))
      (node (ref "RIGHT_PICO_SOCKET") (pin "12") (pinfunction "29_-_GP22_12") (pintype "unspecified"))
    )
    (net (code "81") (name "{slash}ROMS_AS") (class "Default")
      (node (ref "D2") (pin "2") (pinfunction "A_2") (pintype "unspecified"))
      (node (ref "D3") (pin "2") (pinfunction "A_2") (pintype "unspecified"))
      (node (ref "R7") (pin "1") (pinfunction "1_1") (pintype "unspecified"))
      (node (ref "RIGHT_PICO_SOCKET") (pin "10") (pinfunction "31_-_GP26_10") (pintype "unspecified"))
    )
    (net (code "82") (name "{slash}UDS") (class "Default")
      (node (ref "ADDR_BUS_LSB") (pin "2") (pinfunction "A1_2") (pintype "unspecified"))
      (node (ref "CON1") (pin "35") (pinfunction "/UDS_35") (pintype "unspecified"))
    )
    (net (code "83") (name "{slash}WRITE") (class "Default")
      (node (ref "DATA_BUS_LSB") (pin "19") (pinfunction "OE#_19") (pintype "unspecified"))
      (node (ref "DATA_BUS_MSB") (pin "19") (pinfunction "OE#_19") (pintype "unspecified"))
      (node (ref "R1") (pin "2") (pinfunction "2_2") (pintype "unspecified"))
      (node (ref "RIGHT_PICO_SOCKET") (pin "7") (pinfunction "34_-_GP28_7") (pintype "unspecified"))
    )
  )
)
